# Main_ASCII.net
KiCad netlist of a schematic drawn in Altium Designer
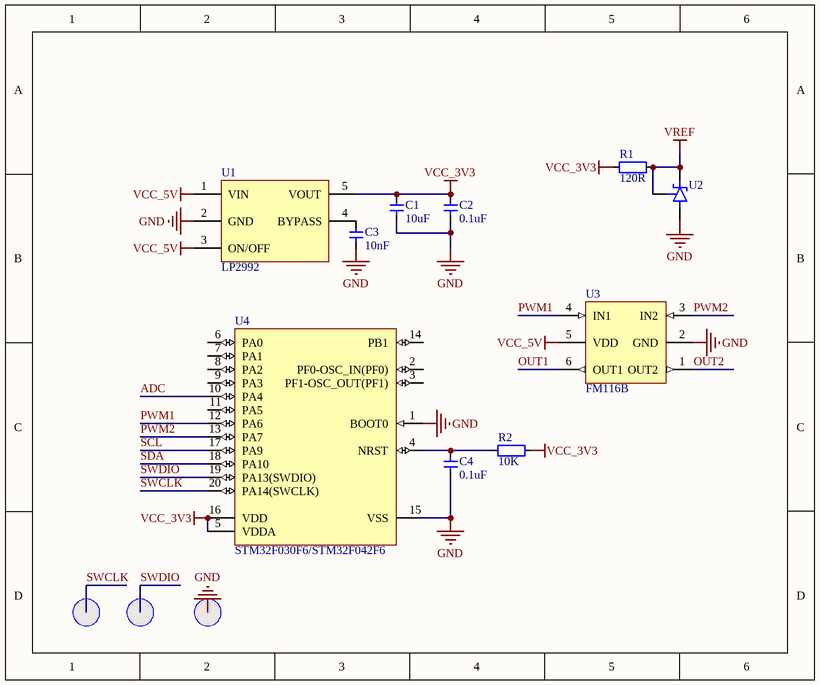
[diagram p0: Main_ASCII.SchDoc]

(export (version "E")
  (design (tool "Eeschema 10.0.6"))
  (components
    (comp (ref "C1")
      (value "10uF")
      (footprint "CAP_0402")
      (description "Capacitor")
      (libsource (lib "MyPcbLib") (part "电容-0402"))
    )
    (comp (ref "C2")
      (value "0.1uF")
      (footprint "CAP_0402")
      (description "Capacitor")
      (libsource (lib "MyPcbLib") (part "电容-0402"))
    )
    (comp (ref "C3")
      (value "10nF")
      (footprint "CAP_0402")
      (description "Capacitor")
      (libsource (lib "MyPcbLib") (part "电容-0402"))
    )
    (comp (ref "C4")
      (value "0.1uF")
      (footprint "CAP_0402")
      (description "Capacitor")
      (libsource (lib "MyPcbLib") (part "电容-0402"))
    )
    (comp (ref "R1")
      (value "120R")
      (footprint "RES_0402")
      (description "Resistor")
      (libsource (lib "MyPcbLib") (part "电阻-0402"))
    )
    (comp (ref "R2")
      (value "10K")
      (footprint "RES_0402")
      (description "Resistor")
      (libsource (lib "") (part "电阻-0402_1"))
    )
    (comp (ref "T1") (value "测试点") (footprint "TEST_PT") (libsource (lib "MyPcbLib") (part "测试点")))
    (comp (ref "T2") (value "测试点") (footprint "TEST_PT") (libsource (lib "MyPcbLib") (part "测试点")))
    (comp (ref "T3") (value "测试点") (footprint "TEST_PT") (libsource (lib "MyPcbLib") (part "测试点")))
    (comp (ref "U1")
      (value "LP2992")
      (footprint "SOT23-5")
      (description "LDO")
      (libsource (lib "MyPcbLib") (part "LP2992"))
    )
    (comp (ref "U2")
      (value "TL431IDBZT")
      (footprint "SOT23-3")
      (description "Adjustable precision shunt regulator 3-SOT-23 -40 to 85")
      (fields (field (name "MF") "Texas Instruments"))
      (libsource (lib "MyPcbLib") (part "TL431IDBZT"))
    )
    (comp (ref "U3")
      (value "FM116B")
      (footprint "SOT23-6")
      (fields (field (name "PARTNUMBER") "24LC256-I/ST"))
      (libsource (lib "MyPcbLib") (part "FM116B"))
    )
    (comp (ref "U4")
      (value "STM32F030F6/STM32F042F6")
      (footprint "TSSOP-20")
      (fields (field (name "PARTNUMBER") "STM32F030F4P6"))
      (libsource (lib "MyPcbLib") (part "STM32F030F4P6"))
    )
  )
  (nets
    (net (code "1") (name "/ADC") (class "Default")
      (node (ref "U4") (pin "10") (pinfunction "PA4_10") (pintype "bidirectional"))
    )
    (net (code "2") (name "/OUT1") (class "Default")
      (node (ref "U3") (pin "6") (pinfunction "OUT1_6") (pintype "output"))
    )
    (net (code "3") (name "/OUT2") (class "Default")
      (node (ref "U3") (pin "1") (pinfunction "OUT2_1") (pintype "output"))
    )
    (net (code "4") (name "/PWM1") (class "Default")
      (node (ref "U3") (pin "4") (pinfunction "IN1_4") (pintype "input"))
      (node (ref "U4") (pin "12") (pinfunction "PA6_12") (pintype "bidirectional"))
    )
    (net (code "5") (name "/PWM2") (class "Default")
      (node (ref "U3") (pin "3") (pinfunction "IN2_3") (pintype "input"))
      (node (ref "U4") (pin "13") (pinfunction "PA7_13") (pintype "bidirectional"))
    )
    (net (code "6") (name "/SCL") (class "Default")
      (node (ref "U4") (pin "17") (pinfunction "PA9_17") (pintype "bidirectional"))
    )
    (net (code "7") (name "/SDA") (class "Default")
      (node (ref "U4") (pin "18") (pinfunction "PA10_18") (pintype "bidirectional"))
    )
    (net (code "8") (name "/SWCLK") (class "Default")
      (node (ref "T1") (pin "0") (pinfunction "0_0") (pintype "passive"))
      (node (ref "U4") (pin "20") (pinfunction "PA14(SWCLK)_20") (pintype "bidirectional"))
    )
    (net (code "9") (name "/SWDIO") (class "Default")
      (node (ref "T2") (pin "0") (pinfunction "0_0") (pintype "passive"))
      (node (ref "U4") (pin "19") (pinfunction "PA13(SWDIO)_19") (pintype "bidirectional"))
    )
    (net (code "10") (name "GND") (class "Default")
      (node (ref "C1") (pin "1") (pinfunction "1_1") (pintype "passive"))
      (node (ref "C2") (pin "1") (pinfunction "1_1") (pintype "passive"))
      (node (ref "C3") (pin "2") (pinfunction "2_2") (pintype "passive"))
      (node (ref "C4") (pin "1") (pinfunction "1_1") (pintype "passive"))
      (node (ref "T3") (pin "0") (pinfunction "0_0") (pintype "passive"))
      (node (ref "U1") (pin "2") (pinfunction "GND_2") (pintype "passive"))
      (node (ref "U2") (pin "3") (pinfunction "ANODE_3") (pintype "passive"))
      (node (ref "U3") (pin "2") (pinfunction "GND_2") (pintype "power_in"))
      (node (ref "U4") (pin "1") (pinfunction "BOOT0_1") (pintype "input"))
      (node (ref "U4") (pin "15") (pinfunction "VSS_15") (pintype "power_in"))
    )
    (net (code "11") (name "Net-(U1-BYPASS)") (class "Default")
      (node (ref "C3") (pin "1") (pinfunction "1_1") (pintype "passive"))
      (node (ref "U1") (pin "4") (pinfunction "BYPASS_4") (pintype "passive"))
    )
    (net (code "12") (name "Net-(U4-NRST)") (class "Default")
      (node (ref "C4") (pin "2") (pinfunction "2_2") (pintype "passive"))
      (node (ref "R2") (pin "2") (pinfunction "2_2") (pintype "passive"))
      (node (ref "U4") (pin "4") (pinfunction "NRST_4") (pintype "bidirectional"))
    )
    (net (code "13") (name "VCC_3V3") (class "Default")
      (node (ref "C1") (pin "2") (pinfunction "2_2") (pintype "passive"))
      (node (ref "C2") (pin "2") (pinfunction "2_2") (pintype "passive"))
      (node (ref "R1") (pin "1") (pinfunction "1_1") (pintype "passive"))
      (node (ref "R2") (pin "1") (pinfunction "1_1") (pintype "passive"))
      (node (ref "U1") (pin "5") (pinfunction "VOUT_5") (pintype "passive"))
      (node (ref "U4") (pin "16") (pinfunction "VDD_16") (pintype "power_in"))
      (node (ref "U4") (pin "5") (pinfunction "VDDA_5") (pintype "power_in"))
    )
    (net (code "14") (name "VCC_5V") (class "Default")
      (node (ref "U1") (pin "1") (pinfunction "VIN_1") (pintype "passive"))
      (node (ref "U1") (pin "3") (pinfunction "ON/OFF_3") (pintype "passive"))
      (node (ref "U3") (pin "5") (pinfunction "VDD_5") (pintype "power_in"))
    )
    (net (code "15") (name "VREF") (class "Default")
      (node (ref "R1") (pin "2") (pinfunction "2_2") (pintype "passive"))
      (node (ref "U2") (pin "1") (pinfunction "CATHODE_1") (pintype "passive"))
      (node (ref "U2") (pin "2") (pinfunction "REF_2") (pintype "passive"))
    )
    (net (code "16") (name "unconnected-(U4-PA0-Pad6)") (class "Default")
      (node (ref "U4") (pin "6") (pinfunction "PA0_6") (pintype "bidirectional"))
    )
    (net (code "17") (name "unconnected-(U4-PA1-Pad7)") (class "Default")
      (node (ref "U4") (pin "7") (pinfunction "PA1_7") (pintype "bidirectional"))
    )
    (net (code "18") (name "unconnected-(U4-PA2-Pad8)") (class "Default")
      (node (ref "U4") (pin "8") (pinfunction "PA2_8") (pintype "bidirectional"))
    )
    (net (code "19") (name "unconnected-(U4-PA3-Pad9)") (class "Default")
      (node (ref "U4") (pin "9") (pinfunction "PA3_9") (pintype "bidirectional"))
    )
    (net (code "20") (name "unconnected-(U4-PA5-Pad11)") (class "Default")
      (node (ref "U4") (pin "11") (pinfunction "PA5_11") (pintype "bidirectional"))
    )
    (net (code "21") (name "unconnected-(U4-PB1-Pad14)") (class "Default")
      (node (ref "U4") (pin "14") (pinfunction "PB1_14") (pintype "bidirectional"))
    )
    (net (code "22") (name "unconnected-(U4-PF0-OSC_IN(PF0)-Pad2)") (class "Default")
      (node (ref "U4") (pin "2") (pinfunction "PF0-OSC_IN(PF0)_2") (pintype "bidirectional"))
    )
    (net (code "23") (name "unconnected-(U4-PF1-OSC_OUT(PF1)-Pad3)") (class "Default")
      (node (ref "U4") (pin "3") (pinfunction "PF1-OSC_OUT(PF1)_3") (pintype "bidirectional"))
    )
  )
)
